# sla2216-conn-dut.net
KiCad netlist of a schematic drawn in Altium Designer
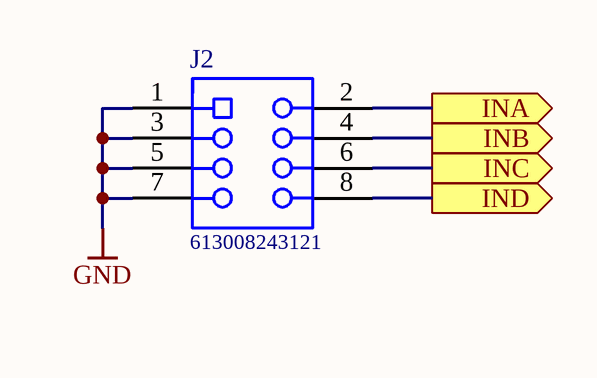
[diagram p0: sla2216-conn-dut.SchDoc]

(export (version "E")
  (design (tool "Eeschema 10.0.6"))
  (components
    (comp (ref "J2")
      (value "613008243121")
      (footprint "613008243121")
      (description "THT Angled Socket Header WR-PHD, Pitch 2.54 mm, Dual Row, 8 pins")
      (fields (field (name "MANUFACTURER") "Wurth Elektronik") (field (name "PUBLISHER") "WurthElektronik"))
      (libsource (lib "Altium Content Vault") (part "WE-CN-2P-F-R8"))
    )
  )
  (nets
    (net (code "1") (name "/INA") (class "Default")
      (node (ref "J2") (pin "2") (pinfunction "2_2") (pintype "passive"))
    )
    (net (code "2") (name "/INB") (class "Default")
      (node (ref "J2") (pin "4") (pinfunction "4_4") (pintype "passive"))
    )
    (net (code "3") (name "/INC") (class "Default")
      (node (ref "J2") (pin "6") (pinfunction "6_6") (pintype "passive"))
    )
    (net (code "4") (name "/IND") (class "Default")
      (node (ref "J2") (pin "8") (pinfunction "8_8") (pintype "passive"))
    )
    (net (code "5") (name "GND") (class "Default")
      (node (ref "J2") (pin "1") (pinfunction "1_1") (pintype "passive"))
      (node (ref "J2") (pin "3") (pinfunction "3_3") (pintype "passive"))
      (node (ref "J2") (pin "5") (pinfunction "5_5") (pintype "passive"))
      (node (ref "J2") (pin "7") (pinfunction "7_7") (pintype "passive"))
    )
  )
)
